# IO_Headers.net
KiCad netlist of a schematic drawn in Altium Designer
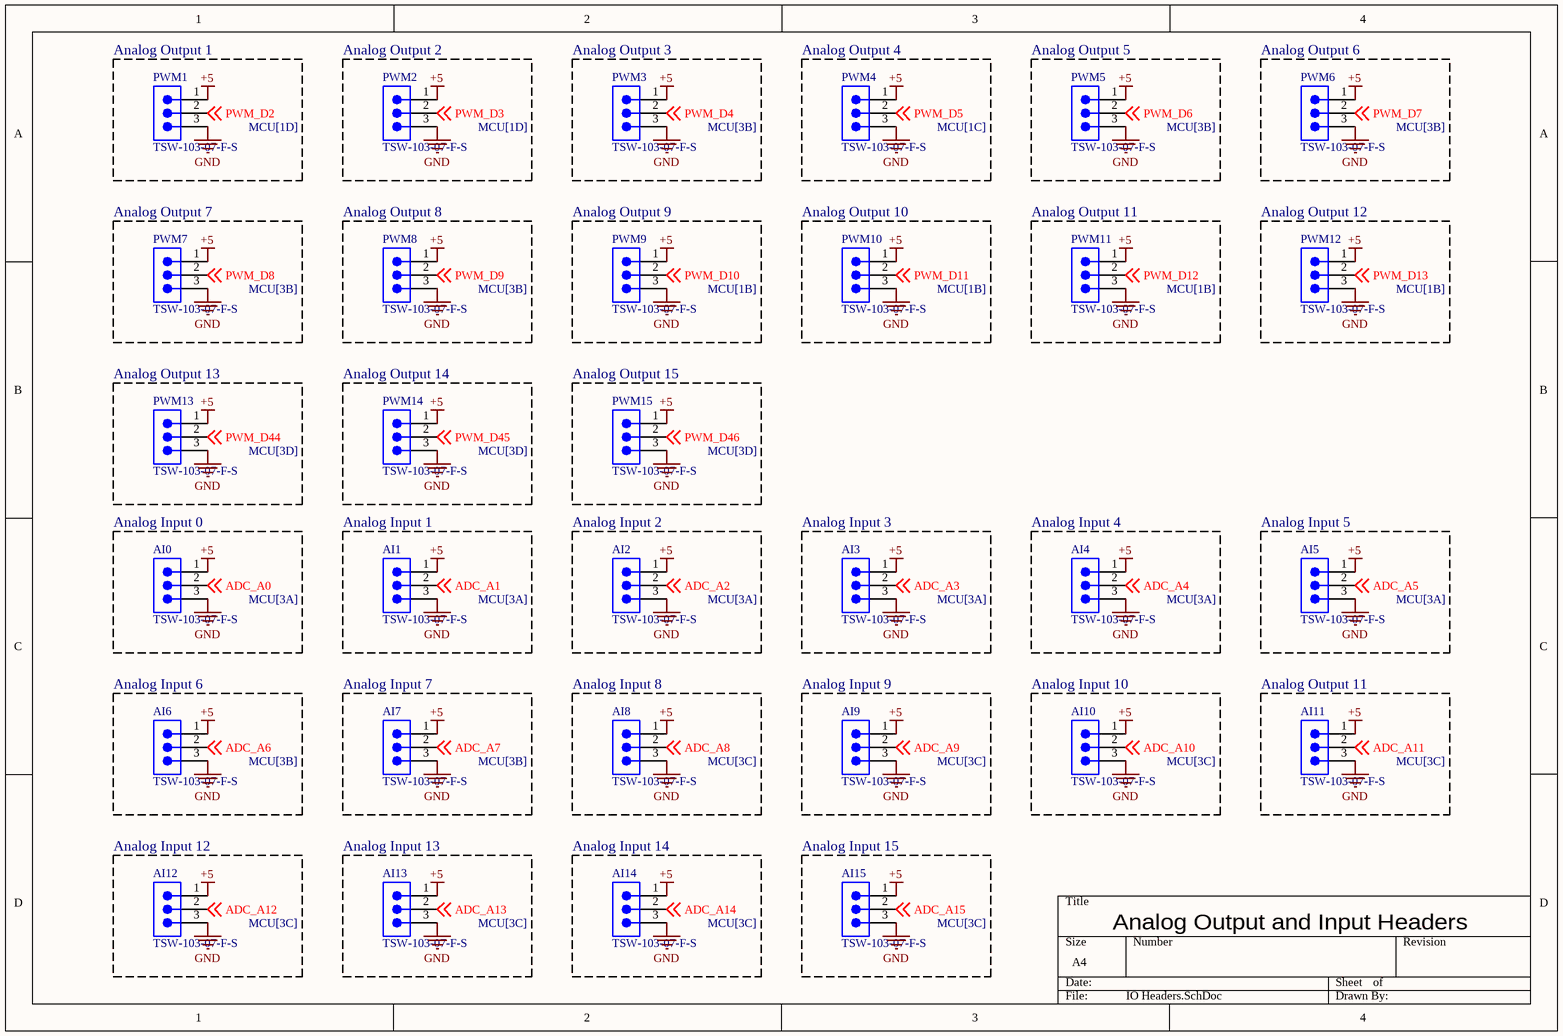
[diagram p0: IO Headers.SchDoc]

(export (version "E")
  (design (tool "Eeschema 10.0.6"))
  (components
    (comp (ref "AI0")
      (value "TSW-103-07-F-S")
      (footprint "SMTC-TSW-103-07-X-S")
      (description "0.025\" SQ Post Header, Through-hole, Vertical, -55 to 125 degC, 2.54 mm Pitch, 3-Pin, Male, RoHS")
      (fields (field (name "MANUFACTURER") "Samtec"))
      (libsource (lib "Altium Content Vault") (part "SMTC-TSW-103-X-X-S-X"))
    )
    (comp (ref "AI1")
      (value "TSW-103-07-F-S")
      (footprint "SMTC-TSW-103-07-X-S")
      (description "0.025\" SQ Post Header, Through-hole, Vertical, -55 to 125 degC, 2.54 mm Pitch, 3-Pin, Male, RoHS")
      (fields (field (name "MANUFACTURER") "Samtec"))
      (libsource (lib "Altium Content Vault") (part "SMTC-TSW-103-X-X-S-X"))
    )
    (comp (ref "AI2")
      (value "TSW-103-07-F-S")
      (footprint "SMTC-TSW-103-07-X-S")
      (description "0.025\" SQ Post Header, Through-hole, Vertical, -55 to 125 degC, 2.54 mm Pitch, 3-Pin, Male, RoHS")
      (fields (field (name "MANUFACTURER") "Samtec"))
      (libsource (lib "Altium Content Vault") (part "SMTC-TSW-103-X-X-S-X"))
    )
    (comp (ref "AI3")
      (value "TSW-103-07-F-S")
      (footprint "SMTC-TSW-103-07-X-S")
      (description "0.025\" SQ Post Header, Through-hole, Vertical, -55 to 125 degC, 2.54 mm Pitch, 3-Pin, Male, RoHS")
      (fields (field (name "MANUFACTURER") "Samtec"))
      (libsource (lib "Altium Content Vault") (part "SMTC-TSW-103-X-X-S-X"))
    )
    (comp (ref "AI4")
      (value "TSW-103-07-F-S")
      (footprint "SMTC-TSW-103-07-X-S")
      (description "0.025\" SQ Post Header, Through-hole, Vertical, -55 to 125 degC, 2.54 mm Pitch, 3-Pin, Male, RoHS")
      (fields (field (name "MANUFACTURER") "Samtec"))
      (libsource (lib "Altium Content Vault") (part "SMTC-TSW-103-X-X-S-X"))
    )
    (comp (ref "AI5")
      (value "TSW-103-07-F-S")
      (footprint "SMTC-TSW-103-07-X-S")
      (description "0.025\" SQ Post Header, Through-hole, Vertical, -55 to 125 degC, 2.54 mm Pitch, 3-Pin, Male, RoHS")
      (fields (field (name "MANUFACTURER") "Samtec"))
      (libsource (lib "Altium Content Vault") (part "SMTC-TSW-103-X-X-S-X"))
    )
    (comp (ref "AI6")
      (value "TSW-103-07-F-S")
      (footprint "SMTC-TSW-103-07-X-S")
      (description "0.025\" SQ Post Header, Through-hole, Vertical, -55 to 125 degC, 2.54 mm Pitch, 3-Pin, Male, RoHS")
      (fields (field (name "MANUFACTURER") "Samtec"))
      (libsource (lib "Altium Content Vault") (part "SMTC-TSW-103-X-X-S-X"))
    )
    (comp (ref "AI7")
      (value "TSW-103-07-F-S")
      (footprint "SMTC-TSW-103-07-X-S")
      (description "0.025\" SQ Post Header, Through-hole, Vertical, -55 to 125 degC, 2.54 mm Pitch, 3-Pin, Male, RoHS")
      (fields (field (name "MANUFACTURER") "Samtec"))
      (libsource (lib "Altium Content Vault") (part "SMTC-TSW-103-X-X-S-X"))
    )
    (comp (ref "AI8")
      (value "TSW-103-07-F-S")
      (footprint "SMTC-TSW-103-07-X-S")
      (description "0.025\" SQ Post Header, Through-hole, Vertical, -55 to 125 degC, 2.54 mm Pitch, 3-Pin, Male, RoHS")
      (fields (field (name "MANUFACTURER") "Samtec"))
      (libsource (lib "Altium Content Vault") (part "SMTC-TSW-103-X-X-S-X"))
    )
    (comp (ref "AI9")
      (value "TSW-103-07-F-S")
      (footprint "SMTC-TSW-103-07-X-S")
      (description "0.025\" SQ Post Header, Through-hole, Vertical, -55 to 125 degC, 2.54 mm Pitch, 3-Pin, Male, RoHS")
      (fields (field (name "MANUFACTURER") "Samtec"))
      (libsource (lib "Altium Content Vault") (part "SMTC-TSW-103-X-X-S-X"))
    )
    (comp (ref "AI10")
      (value "TSW-103-07-F-S")
      (footprint "SMTC-TSW-103-07-X-S")
      (description "0.025\" SQ Post Header, Through-hole, Vertical, -55 to 125 degC, 2.54 mm Pitch, 3-Pin, Male, RoHS")
      (fields (field (name "MANUFACTURER") "Samtec"))
      (libsource (lib "Altium Content Vault") (part "SMTC-TSW-103-X-X-S-X"))
    )
    (comp (ref "AI11")
      (value "TSW-103-07-F-S")
      (footprint "SMTC-TSW-103-07-X-S")
      (description "0.025\" SQ Post Header, Through-hole, Vertical, -55 to 125 degC, 2.54 mm Pitch, 3-Pin, Male, RoHS")
      (fields (field (name "MANUFACTURER") "Samtec"))
      (libsource (lib "Altium Content Vault") (part "SMTC-TSW-103-X-X-S-X"))
    )
    (comp (ref "AI12")
      (value "TSW-103-07-F-S")
      (footprint "SMTC-TSW-103-07-X-S")
      (description "0.025\" SQ Post Header, Through-hole, Vertical, -55 to 125 degC, 2.54 mm Pitch, 3-Pin, Male, RoHS")
      (fields (field (name "MANUFACTURER") "Samtec"))
      (libsource (lib "Altium Content Vault") (part "SMTC-TSW-103-X-X-S-X"))
    )
    (comp (ref "AI13")
      (value "TSW-103-07-F-S")
      (footprint "SMTC-TSW-103-07-X-S")
      (description "0.025\" SQ Post Header, Through-hole, Vertical, -55 to 125 degC, 2.54 mm Pitch, 3-Pin, Male, RoHS")
      (fields (field (name "MANUFACTURER") "Samtec"))
      (libsource (lib "Altium Content Vault") (part "SMTC-TSW-103-X-X-S-X"))
    )
    (comp (ref "AI14")
      (value "TSW-103-07-F-S")
      (footprint "SMTC-TSW-103-07-X-S")
      (description "0.025\" SQ Post Header, Through-hole, Vertical, -55 to 125 degC, 2.54 mm Pitch, 3-Pin, Male, RoHS")
      (fields (field (name "MANUFACTURER") "Samtec"))
      (libsource (lib "Altium Content Vault") (part "SMTC-TSW-103-X-X-S-X"))
    )
    (comp (ref "AI15")
      (value "TSW-103-07-F-S")
      (footprint "SMTC-TSW-103-07-X-S")
      (description "0.025\" SQ Post Header, Through-hole, Vertical, -55 to 125 degC, 2.54 mm Pitch, 3-Pin, Male, RoHS")
      (fields (field (name "MANUFACTURER") "Samtec"))
      (libsource (lib "Altium Content Vault") (part "SMTC-TSW-103-X-X-S-X"))
    )
    (comp (ref "PWM1")
      (value "TSW-103-07-F-S")
      (footprint "SMTC-TSW-103-07-X-S")
      (description "0.025\" SQ Post Header, Through-hole, Vertical, -55 to 125 degC, 2.54 mm Pitch, 3-Pin, Male, RoHS")
      (fields (field (name "MANUFACTURER") "Samtec"))
      (libsource (lib "Altium Content Vault") (part "SMTC-TSW-103-X-X-S-X"))
    )
    (comp (ref "PWM2")
      (value "TSW-103-07-F-S")
      (footprint "SMTC-TSW-103-07-X-S")
      (description "0.025\" SQ Post Header, Through-hole, Vertical, -55 to 125 degC, 2.54 mm Pitch, 3-Pin, Male, RoHS")
      (fields (field (name "MANUFACTURER") "Samtec"))
      (libsource (lib "Altium Content Vault") (part "SMTC-TSW-103-X-X-S-X"))
    )
    (comp (ref "PWM3")
      (value "TSW-103-07-F-S")
      (footprint "SMTC-TSW-103-07-X-S")
      (description "0.025\" SQ Post Header, Through-hole, Vertical, -55 to 125 degC, 2.54 mm Pitch, 3-Pin, Male, RoHS")
      (fields (field (name "MANUFACTURER") "Samtec"))
      (libsource (lib "Altium Content Vault") (part "SMTC-TSW-103-X-X-S-X"))
    )
    (comp (ref "PWM4")
      (value "TSW-103-07-F-S")
      (footprint "SMTC-TSW-103-07-X-S")
      (description "0.025\" SQ Post Header, Through-hole, Vertical, -55 to 125 degC, 2.54 mm Pitch, 3-Pin, Male, RoHS")
      (fields (field (name "MANUFACTURER") "Samtec"))
      (libsource (lib "Altium Content Vault") (part "SMTC-TSW-103-X-X-S-X"))
    )
    (comp (ref "PWM5")
      (value "TSW-103-07-F-S")
      (footprint "SMTC-TSW-103-07-X-S")
      (description "0.025\" SQ Post Header, Through-hole, Vertical, -55 to 125 degC, 2.54 mm Pitch, 3-Pin, Male, RoHS")
      (fields (field (name "MANUFACTURER") "Samtec"))
      (libsource (lib "Altium Content Vault") (part "SMTC-TSW-103-X-X-S-X"))
    )
    (comp (ref "PWM6")
      (value "TSW-103-07-F-S")
      (footprint "SMTC-TSW-103-07-X-S")
      (description "0.025\" SQ Post Header, Through-hole, Vertical, -55 to 125 degC, 2.54 mm Pitch, 3-Pin, Male, RoHS")
      (fields (field (name "MANUFACTURER") "Samtec"))
      (libsource (lib "Altium Content Vault") (part "SMTC-TSW-103-X-X-S-X"))
    )
    (comp (ref "PWM7")
      (value "TSW-103-07-F-S")
      (footprint "SMTC-TSW-103-07-X-S")
      (description "0.025\" SQ Post Header, Through-hole, Vertical, -55 to 125 degC, 2.54 mm Pitch, 3-Pin, Male, RoHS")
      (fields (field (name "MANUFACTURER") "Samtec"))
      (libsource (lib "Altium Content Vault") (part "SMTC-TSW-103-X-X-S-X"))
    )
    (comp (ref "PWM8")
      (value "TSW-103-07-F-S")
      (footprint "SMTC-TSW-103-07-X-S")
      (description "0.025\" SQ Post Header, Through-hole, Vertical, -55 to 125 degC, 2.54 mm Pitch, 3-Pin, Male, RoHS")
      (fields (field (name "MANUFACTURER") "Samtec"))
      (libsource (lib "Altium Content Vault") (part "SMTC-TSW-103-X-X-S-X"))
    )
    (comp (ref "PWM9")
      (value "TSW-103-07-F-S")
      (footprint "SMTC-TSW-103-07-X-S")
      (description "0.025\" SQ Post Header, Through-hole, Vertical, -55 to 125 degC, 2.54 mm Pitch, 3-Pin, Male, RoHS")
      (fields (field (name "MANUFACTURER") "Samtec"))
      (libsource (lib "Altium Content Vault") (part "SMTC-TSW-103-X-X-S-X"))
    )
    (comp (ref "PWM10")
      (value "TSW-103-07-F-S")
      (footprint "SMTC-TSW-103-07-X-S")
      (description "0.025\" SQ Post Header, Through-hole, Vertical, -55 to 125 degC, 2.54 mm Pitch, 3-Pin, Male, RoHS")
      (fields (field (name "MANUFACTURER") "Samtec"))
      (libsource (lib "Altium Content Vault") (part "SMTC-TSW-103-X-X-S-X"))
    )
    (comp (ref "PWM11")
      (value "TSW-103-07-F-S")
      (footprint "SMTC-TSW-103-07-X-S")
      (description "0.025\" SQ Post Header, Through-hole, Vertical, -55 to 125 degC, 2.54 mm Pitch, 3-Pin, Male, RoHS")
      (fields (field (name "MANUFACTURER") "Samtec"))
      (libsource (lib "Altium Content Vault") (part "SMTC-TSW-103-X-X-S-X"))
    )
    (comp (ref "PWM12")
      (value "TSW-103-07-F-S")
      (footprint "SMTC-TSW-103-07-X-S")
      (description "0.025\" SQ Post Header, Through-hole, Vertical, -55 to 125 degC, 2.54 mm Pitch, 3-Pin, Male, RoHS")
      (fields (field (name "MANUFACTURER") "Samtec"))
      (libsource (lib "Altium Content Vault") (part "SMTC-TSW-103-X-X-S-X"))
    )
    (comp (ref "PWM13")
      (value "TSW-103-07-F-S")
      (footprint "SMTC-TSW-103-07-X-S")
      (description "0.025\" SQ Post Header, Through-hole, Vertical, -55 to 125 degC, 2.54 mm Pitch, 3-Pin, Male, RoHS")
      (fields (field (name "MANUFACTURER") "Samtec"))
      (libsource (lib "Altium Content Vault") (part "SMTC-TSW-103-X-X-S-X"))
    )
    (comp (ref "PWM14")
      (value "TSW-103-07-F-S")
      (footprint "SMTC-TSW-103-07-X-S")
      (description "0.025\" SQ Post Header, Through-hole, Vertical, -55 to 125 degC, 2.54 mm Pitch, 3-Pin, Male, RoHS")
      (fields (field (name "MANUFACTURER") "Samtec"))
      (libsource (lib "Altium Content Vault") (part "SMTC-TSW-103-X-X-S-X"))
    )
    (comp (ref "PWM15")
      (value "TSW-103-07-F-S")
      (footprint "SMTC-TSW-103-07-X-S")
      (description "0.025\" SQ Post Header, Through-hole, Vertical, -55 to 125 degC, 2.54 mm Pitch, 3-Pin, Male, RoHS")
      (fields (field (name "MANUFACTURER") "Samtec"))
      (libsource (lib "Altium Content Vault") (part "SMTC-TSW-103-X-X-S-X"))
    )
  )
  (nets
    (net (code "1") (name "+5") (class "Default")
      (node (ref "AI0") (pin "1") (pinfunction "1_1") (pintype "passive"))
      (node (ref "AI1") (pin "1") (pinfunction "1_1") (pintype "passive"))
      (node (ref "AI10") (pin "1") (pinfunction "1_1") (pintype "passive"))
      (node (ref "AI11") (pin "1") (pinfunction "1_1") (pintype "passive"))
      (node (ref "AI12") (pin "1") (pinfunction "1_1") (pintype "passive"))
      (node (ref "AI13") (pin "1") (pinfunction "1_1") (pintype "passive"))
      (node (ref "AI14") (pin "1") (pinfunction "1_1") (pintype "passive"))
      (node (ref "AI15") (pin "1") (pinfunction "1_1") (pintype "passive"))
      (node (ref "AI2") (pin "1") (pinfunction "1_1") (pintype "passive"))
      (node (ref "AI3") (pin "1") (pinfunction "1_1") (pintype "passive"))
      (node (ref "AI4") (pin "1") (pinfunction "1_1") (pintype "passive"))
      (node (ref "AI5") (pin "1") (pinfunction "1_1") (pintype "passive"))
      (node (ref "AI6") (pin "1") (pinfunction "1_1") (pintype "passive"))
      (node (ref "AI7") (pin "1") (pinfunction "1_1") (pintype "passive"))
      (node (ref "AI8") (pin "1") (pinfunction "1_1") (pintype "passive"))
      (node (ref "AI9") (pin "1") (pinfunction "1_1") (pintype "passive"))
      (node (ref "PWM1") (pin "1") (pinfunction "1_1") (pintype "passive"))
      (node (ref "PWM10") (pin "1") (pinfunction "1_1") (pintype "passive"))
      (node (ref "PWM11") (pin "1") (pinfunction "1_1") (pintype "passive"))
      (node (ref "PWM12") (pin "1") (pinfunction "1_1") (pintype "passive"))
      (node (ref "PWM13") (pin "1") (pinfunction "1_1") (pintype "passive"))
      (node (ref "PWM14") (pin "1") (pinfunction "1_1") (pintype "passive"))
      (node (ref "PWM15") (pin "1") (pinfunction "1_1") (pintype "passive"))
      (node (ref "PWM2") (pin "1") (pinfunction "1_1") (pintype "passive"))
      (node (ref "PWM3") (pin "1") (pinfunction "1_1") (pintype "passive"))
      (node (ref "PWM4") (pin "1") (pinfunction "1_1") (pintype "passive"))
      (node (ref "PWM5") (pin "1") (pinfunction "1_1") (pintype "passive"))
      (node (ref "PWM6") (pin "1") (pinfunction "1_1") (pintype "passive"))
      (node (ref "PWM7") (pin "1") (pinfunction "1_1") (pintype "passive"))
      (node (ref "PWM8") (pin "1") (pinfunction "1_1") (pintype "passive"))
      (node (ref "PWM9") (pin "1") (pinfunction "1_1") (pintype "passive"))
    )
    (net (code "2") (name "ADC_A0") (class "Default")
      (node (ref "AI0") (pin "2") (pinfunction "2_2") (pintype "passive"))
    )
    (net (code "3") (name "ADC_A1") (class "Default")
      (node (ref "AI1") (pin "2") (pinfunction "2_2") (pintype "passive"))
    )
    (net (code "4") (name "ADC_A2") (class "Default")
      (node (ref "AI2") (pin "2") (pinfunction "2_2") (pintype "passive"))
    )
    (net (code "5") (name "ADC_A3") (class "Default")
      (node (ref "AI3") (pin "2") (pinfunction "2_2") (pintype "passive"))
    )
    (net (code "6") (name "ADC_A4") (class "Default")
      (node (ref "AI4") (pin "2") (pinfunction "2_2") (pintype "passive"))
    )
    (net (code "7") (name "ADC_A5") (class "Default")
      (node (ref "AI5") (pin "2") (pinfunction "2_2") (pintype "passive"))
    )
    (net (code "8") (name "ADC_A6") (class "Default")
      (node (ref "AI6") (pin "2") (pinfunction "2_2") (pintype "passive"))
    )
    (net (code "9") (name "ADC_A7") (class "Default")
      (node (ref "AI7") (pin "2") (pinfunction "2_2") (pintype "passive"))
    )
    (net (code "10") (name "ADC_A8") (class "Default")
      (node (ref "AI8") (pin "2") (pinfunction "2_2") (pintype "passive"))
    )
    (net (code "11") (name "ADC_A9") (class "Default")
      (node (ref "AI9") (pin "2") (pinfunction "2_2") (pintype "passive"))
    )
    (net (code "12") (name "ADC_A10") (class "Default")
      (node (ref "AI10") (pin "2") (pinfunction "2_2") (pintype "passive"))
    )
    (net (code "13") (name "ADC_A11") (class "Default")
      (node (ref "AI11") (pin "2") (pinfunction "2_2") (pintype "passive"))
    )
    (net (code "14") (name "ADC_A12") (class "Default")
      (node (ref "AI12") (pin "2") (pinfunction "2_2") (pintype "passive"))
    )
    (net (code "15") (name "ADC_A13") (class "Default")
      (node (ref "AI13") (pin "2") (pinfunction "2_2") (pintype "passive"))
    )
    (net (code "16") (name "ADC_A14") (class "Default")
      (node (ref "AI14") (pin "2") (pinfunction "2_2") (pintype "passive"))
    )
    (net (code "17") (name "ADC_A15") (class "Default")
      (node (ref "AI15") (pin "2") (pinfunction "2_2") (pintype "passive"))
    )
    (net (code "18") (name "GND") (class "Default")
      (node (ref "AI0") (pin "3") (pinfunction "3_3") (pintype "passive"))
      (node (ref "AI1") (pin "3") (pinfunction "3_3") (pintype "passive"))
      (node (ref "AI10") (pin "3") (pinfunction "3_3") (pintype "passive"))
      (node (ref "AI11") (pin "3") (pinfunction "3_3") (pintype "passive"))
      (node (ref "AI12") (pin "3") (pinfunction "3_3") (pintype "passive"))
      (node (ref "AI13") (pin "3") (pinfunction "3_3") (pintype "passive"))
      (node (ref "AI14") (pin "3") (pinfunction "3_3") (pintype "passive"))
      (node (ref "AI15") (pin "3") (pinfunction "3_3") (pintype "passive"))
      (node (ref "AI2") (pin "3") (pinfunction "3_3") (pintype "passive"))
      (node (ref "AI3") (pin "3") (pinfunction "3_3") (pintype "passive"))
      (node (ref "AI4") (pin "3") (pinfunction "3_3") (pintype "passive"))
      (node (ref "AI5") (pin "3") (pinfunction "3_3") (pintype "passive"))
      (node (ref "AI6") (pin "3") (pinfunction "3_3") (pintype "passive"))
      (node (ref "AI7") (pin "3") (pinfunction "3_3") (pintype "passive"))
      (node (ref "AI8") (pin "3") (pinfunction "3_3") (pintype "passive"))
      (node (ref "AI9") (pin "3") (pinfunction "3_3") (pintype "passive"))
      (node (ref "PWM1") (pin "3") (pinfunction "3_3") (pintype "passive"))
      (node (ref "PWM10") (pin "3") (pinfunction "3_3") (pintype "passive"))
      (node (ref "PWM11") (pin "3") (pinfunction "3_3") (pintype "passive"))
      (node (ref "PWM12") (pin "3") (pinfunction "3_3") (pintype "passive"))
      (node (ref "PWM13") (pin "3") (pinfunction "3_3") (pintype "passive"))
      (node (ref "PWM14") (pin "3") (pinfunction "3_3") (pintype "passive"))
      (node (ref "PWM15") (pin "3") (pinfunction "3_3") (pintype "passive"))
      (node (ref "PWM2") (pin "3") (pinfunction "3_3") (pintype "passive"))
      (node (ref "PWM3") (pin "3") (pinfunction "3_3") (pintype "passive"))
      (node (ref "PWM4") (pin "3") (pinfunction "3_3") (pintype "passive"))
      (node (ref "PWM5") (pin "3") (pinfunction "3_3") (pintype "passive"))
      (node (ref "PWM6") (pin "3") (pinfunction "3_3") (pintype "passive"))
      (node (ref "PWM7") (pin "3") (pinfunction "3_3") (pintype "passive"))
      (node (ref "PWM8") (pin "3") (pinfunction "3_3") (pintype "passive"))
      (node (ref "PWM9") (pin "3") (pinfunction "3_3") (pintype "passive"))
    )
    (net (code "19") (name "PWM_D2") (class "Default")
      (node (ref "PWM1") (pin "2") (pinfunction "2_2") (pintype "passive"))
    )
    (net (code "20") (name "PWM_D3") (class "Default")
      (node (ref "PWM2") (pin "2") (pinfunction "2_2") (pintype "passive"))
    )
    (net (code "21") (name "PWM_D4") (class "Default")
      (node (ref "PWM3") (pin "2") (pinfunction "2_2") (pintype "passive"))
    )
    (net (code "22") (name "PWM_D5") (class "Default")
      (node (ref "PWM4") (pin "2") (pinfunction "2_2") (pintype "passive"))
    )
    (net (code "23") (name "PWM_D6") (class "Default")
      (node (ref "PWM5") (pin "2") (pinfunction "2_2") (pintype "passive"))
    )
    (net (code "24") (name "PWM_D7") (class "Default")
      (node (ref "PWM6") (pin "2") (pinfunction "2_2") (pintype "passive"))
    )
    (net (code "25") (name "PWM_D8") (class "Default")
      (node (ref "PWM7") (pin "2") (pinfunction "2_2") (pintype "passive"))
    )
    (net (code "26") (name "PWM_D9") (class "Default")
      (node (ref "PWM8") (pin "2") (pinfunction "2_2") (pintype "passive"))
    )
    (net (code "27") (name "PWM_D10") (class "Default")
      (node (ref "PWM9") (pin "2") (pinfunction "2_2") (pintype "passive"))
    )
    (net (code "28") (name "PWM_D11") (class "Default")
      (node (ref "PWM10") (pin "2") (pinfunction "2_2") (pintype "passive"))
    )
    (net (code "29") (name "PWM_D12") (class "Default")
      (node (ref "PWM11") (pin "2") (pinfunction "2_2") (pintype "passive"))
    )
    (net (code "30") (name "PWM_D13") (class "Default")
      (node (ref "PWM12") (pin "2") (pinfunction "2_2") (pintype "passive"))
    )
    (net (code "31") (name "PWM_D44") (class "Default")
      (node (ref "PWM13") (pin "2") (pinfunction "2_2") (pintype "passive"))
    )
    (net (code "32") (name "PWM_D45") (class "Default")
      (node (ref "PWM14") (pin "2") (pinfunction "2_2") (pintype "passive"))
    )
    (net (code "33") (name "PWM_D46") (class "Default")
      (node (ref "PWM15") (pin "2") (pinfunction "2_2") (pintype "passive"))
    )
  )
)
